# SPv2_2.net
KiCad netlist of a schematic drawn in EAGLE
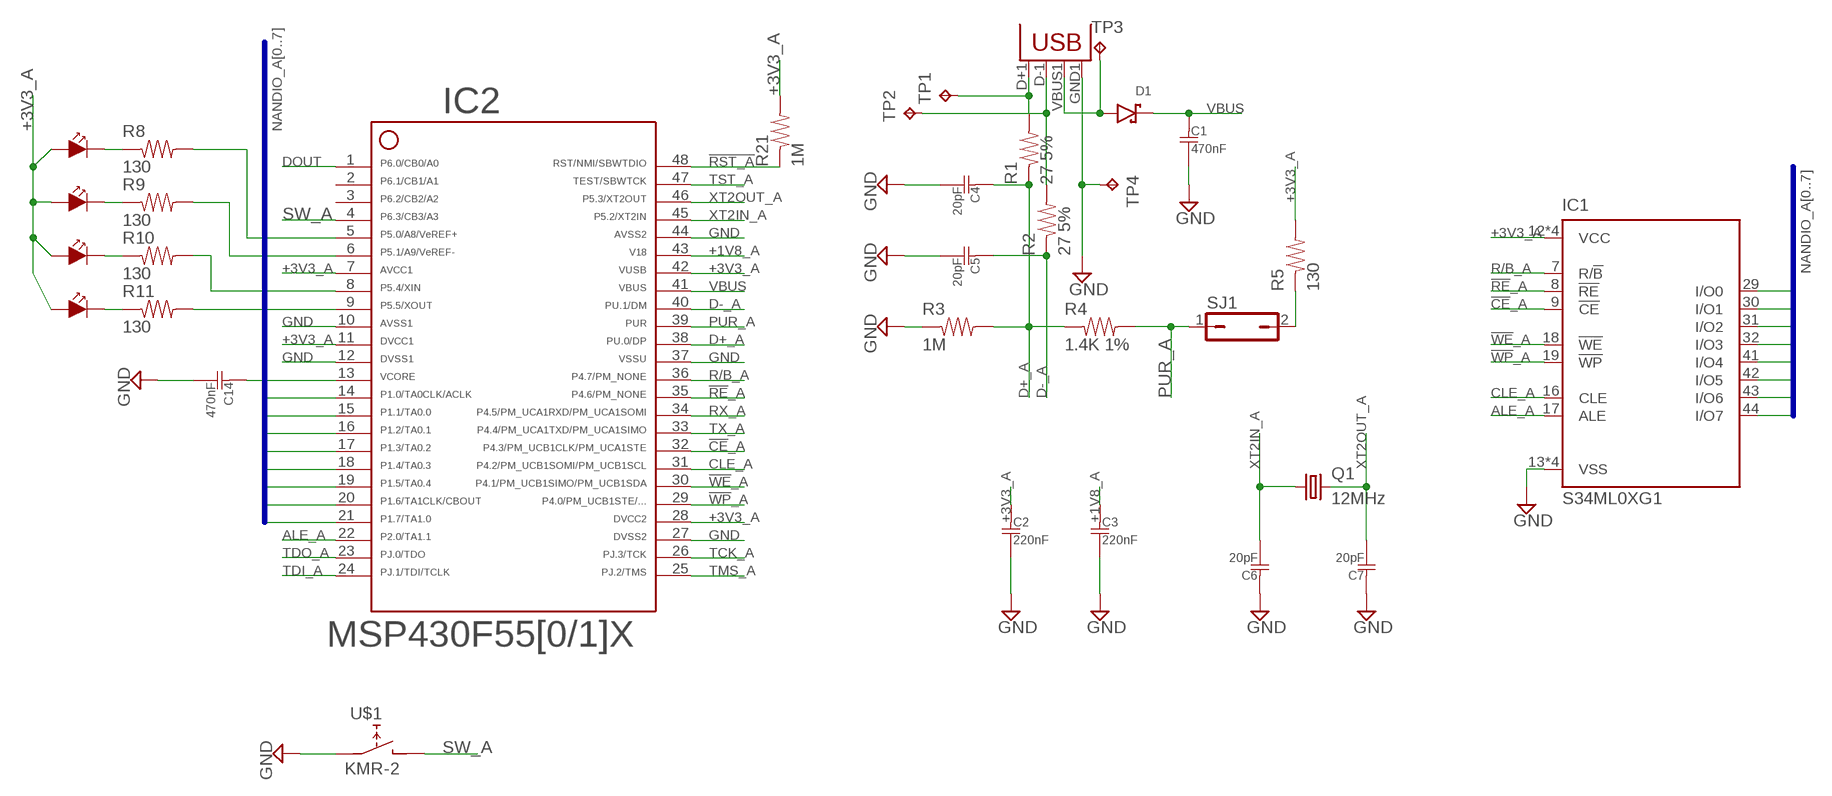
[diagram p0: schematic, sheet 1]
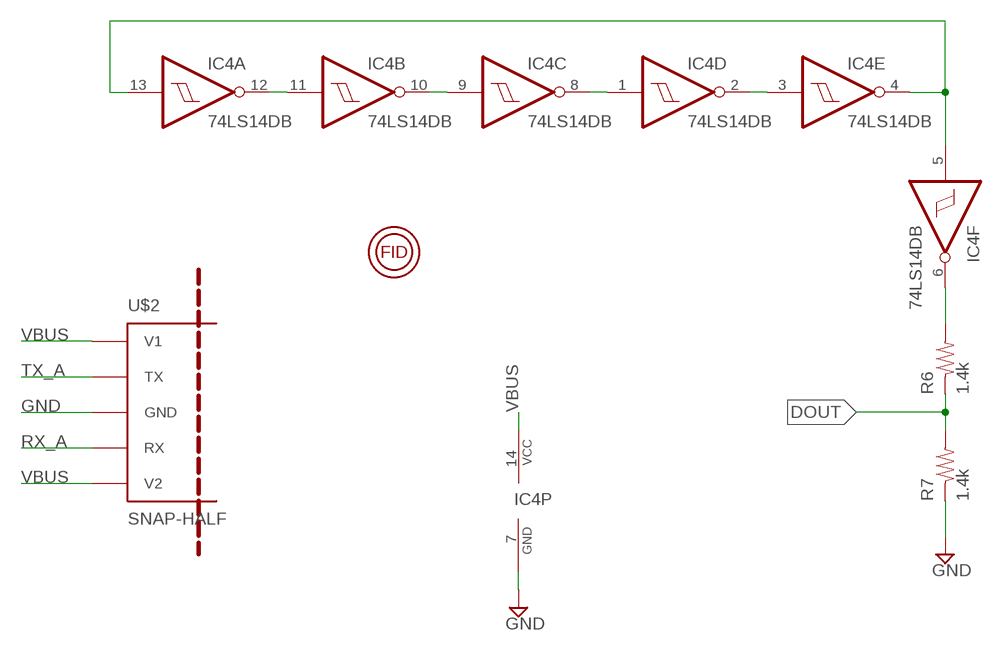
[diagram p1: schematic, sheet 2]

(export (version "E")
  (design (tool "Eeschema 10.0.6"))
  (components
    (comp (ref "IC4")
      (value "74LS14DB")
      (footprint "eagle-import:SSOP14")
      (libsource (lib "eagle-import") (part "7414DBLS"))
    )
    (comp (ref "R6")
      (value "1.4k")
      (footprint "eagle-import:R0805")
      (libsource (lib "eagle-import") (part "R0805"))
    )
    (comp (ref "R7")
      (value "1.4k")
      (footprint "eagle-import:R0805")
      (libsource (lib "eagle-import") (part "R0805"))
    )
    (comp (ref "U$2")
      (value "SNAP-HALF")
      (footprint "eagle-import:SNAP-HALF")
      (libsource (lib "eagle-import") (part "SNAP-HALF"))
    )
    (comp (ref "U$3")
      (value "FIDUCAL")
      (footprint "eagle-import:FIDUCAL")
      (libsource (lib "eagle-import") (part "FIDUCAL"))
    )
    (comp (ref "C1")
      (value "470nF")
      (footprint "eagle-import:R0805")
      (libsource (lib "eagle-import") (part "C0805"))
    )
    (comp (ref "C2")
      (value "220nF")
      (footprint "eagle-import:R0805")
      (libsource (lib "eagle-import") (part "C0805"))
    )
    (comp (ref "C3")
      (value "220nF")
      (footprint "eagle-import:R0805")
      (libsource (lib "eagle-import") (part "C0805"))
    )
    (comp (ref "C4")
      (value "20pF")
      (footprint "eagle-import:R0805")
      (libsource (lib "eagle-import") (part "C0805"))
    )
    (comp (ref "C5")
      (value "20pF")
      (footprint "eagle-import:R0805")
      (libsource (lib "eagle-import") (part "C0805"))
    )
    (comp (ref "C6")
      (value "20pF")
      (footprint "eagle-import:R0805")
      (libsource (lib "eagle-import") (part "C0805"))
    )
    (comp (ref "C7")
      (value "20pF")
      (footprint "eagle-import:R0805")
      (libsource (lib "eagle-import") (part "C0805"))
    )
    (comp (ref "C14")
      (value "470nF")
      (footprint "eagle-import:R0805")
      (libsource (lib "eagle-import") (part "C0805"))
    )
    (comp (ref "D1")
      (value "D-SCHOTTKY")
      (footprint "eagle-import:SOD123")
      (libsource (lib "eagle-import") (part "D-SCHOTTKY"))
    )
    (comp (ref "IC1")
      (value "S34ML0XG1")
      (footprint "eagle-import:TSOP48")
      (libsource (lib "eagle-import") (part "S34ML0XG1"))
    )
    (comp (ref "IC2")
      (value "F5508")
      (footprint "eagle-import:PT48")
      (libsource (lib "eagle-import") (part "F55[0/1]X---PT48"))
    )
    (comp (ref "JP1")
      (value "USBA-SMD-MALE")
      (footprint "eagle-import:USB-A-SMT-MALE")
      (libsource (lib "eagle-import") (part "USBA-SMD-MALE"))
    )
    (comp (ref "Q1")
      (value "12MHz")
      (footprint "eagle-import:CSM-3X")
      (libsource (lib "eagle-import") (part "CRYSTALCSM-3X"))
    )
    (comp (ref "R1")
      (value "27 5%")
      (footprint "eagle-import:R0805")
      (libsource (lib "eagle-import") (part "R0805"))
    )
    (comp (ref "R2")
      (value "27 5%")
      (footprint "eagle-import:R0805")
      (libsource (lib "eagle-import") (part "R0805"))
    )
    (comp (ref "R3")
      (value "1M")
      (footprint "eagle-import:R0805")
      (libsource (lib "eagle-import") (part "R0805"))
    )
    (comp (ref "R4")
      (value "1.4K 1%")
      (footprint "eagle-import:R0805")
      (libsource (lib "eagle-import") (part "R0805"))
    )
    (comp (ref "R5")
      (value "130")
      (footprint "eagle-import:R0805")
      (libsource (lib "eagle-import") (part "R0805"))
    )
    (comp (ref "R8")
      (value "130")
      (footprint "eagle-import:R0805")
      (libsource (lib "eagle-import") (part "R0805"))
    )
    (comp (ref "R9")
      (value "130")
      (footprint "eagle-import:R0805")
      (libsource (lib "eagle-import") (part "R0805"))
    )
    (comp (ref "R10")
      (value "130")
      (footprint "eagle-import:R0805")
      (libsource (lib "eagle-import") (part "R0805"))
    )
    (comp (ref "R11")
      (value "130")
      (footprint "eagle-import:R0805")
      (libsource (lib "eagle-import") (part "R0805"))
    )
    (comp (ref "R21")
      (value "1M")
      (footprint "eagle-import:R0805")
      (libsource (lib "eagle-import") (part "R0805"))
    )
    (comp (ref "SJ1")
      (value "JP1Q")
      (footprint "eagle-import:JP1")
      (libsource (lib "eagle-import") (part "JP1Q"))
    )
    (comp (ref "TP1")
      (value "TPTP13R")
      (footprint "eagle-import:TP13R")
      (libsource (lib "eagle-import") (part "TPTP13R"))
    )
    (comp (ref "TP2")
      (value "TPTP13R")
      (footprint "eagle-import:TP13R")
      (libsource (lib "eagle-import") (part "TPTP13R"))
    )
    (comp (ref "TP3")
      (value "TPTP13R")
      (footprint "eagle-import:TP13R")
      (libsource (lib "eagle-import") (part "TPTP13R"))
    )
    (comp (ref "TP4")
      (value "TPTP13R")
      (footprint "eagle-import:TP13R")
      (libsource (lib "eagle-import") (part "TPTP13R"))
    )
    (comp (ref "U$1")
      (value "KMR-2")
      (footprint "eagle-import:KMR-2-SWITCH")
      (libsource (lib "eagle-import") (part "KMR-2"))
    )
    (comp (ref "U$5")
      (value "LED")
      (footprint "eagle-import:LED0805")
      (libsource (lib "eagle-import") (part "LED"))
    )
    (comp (ref "U$6")
      (value "LED")
      (footprint "eagle-import:LED0805")
      (libsource (lib "eagle-import") (part "LED"))
    )
    (comp (ref "U$7")
      (value "LED")
      (footprint "eagle-import:LED0805")
      (libsource (lib "eagle-import") (part "LED"))
    )
    (comp (ref "U$8")
      (value "LED")
      (footprint "eagle-import:LED0805")
      (libsource (lib "eagle-import") (part "LED"))
    )
  )
  (nets
    (net (code "1") (name "+1V8_A") (class "Default")
      (node (ref "C3") (pin "P$1") (pinfunction "1_P$1") (pintype "passive"))
      (node (ref "IC2") (pin "43") (pinfunction "43_43") (pintype "power_in"))
    )
    (net (code "2") (name "+3V3_A") (class "Default")
      (node (ref "C2") (pin "P$1") (pinfunction "1_P$1") (pintype "passive"))
      (node (ref "IC1") (pin "12") (pinfunction "VCC_12") (pintype "power_in"))
      (node (ref "IC1") (pin "34") (pinfunction "VCC_34") (pintype "power_in"))
      (node (ref "IC1") (pin "37") (pinfunction "VCC_37") (pintype "power_in"))
      (node (ref "IC1") (pin "39") (pinfunction "VCC_39") (pintype "power_in"))
      (node (ref "IC2") (pin "11") (pinfunction "11_11") (pintype "power_in"))
      (node (ref "IC2") (pin "28") (pinfunction "28_28") (pintype "power_in"))
      (node (ref "IC2") (pin "42") (pinfunction "42_42") (pintype "power_in"))
      (node (ref "IC2") (pin "7") (pinfunction "7_7") (pintype "power_in"))
      (node (ref "R21") (pin "P$2") (pinfunction "2_P$2") (pintype "passive"))
      (node (ref "R5") (pin "P$2") (pinfunction "2_P$2") (pintype "passive"))
      (node (ref "U$5") (pin "ANODE") (pinfunction "ANODE_ANODE") (pintype "passive"))
      (node (ref "U$6") (pin "ANODE") (pinfunction "ANODE_ANODE") (pintype "passive"))
      (node (ref "U$7") (pin "ANODE") (pinfunction "ANODE_ANODE") (pintype "passive"))
      (node (ref "U$8") (pin "ANODE") (pinfunction "ANODE_ANODE") (pintype "passive"))
    )
    (net (code "4") (name "ALE_A") (class "Default")
      (node (ref "IC1") (pin "17") (pinfunction "ALE_17") (pintype "input"))
      (node (ref "IC2") (pin "22") (pinfunction "22_22") (pintype "bidirectional"))
    )
    (net (code "5") (name "CLE_A") (class "Default")
      (node (ref "IC1") (pin "16") (pinfunction "CLE_16") (pintype "input"))
      (node (ref "IC2") (pin "31") (pinfunction "31_31") (pintype "bidirectional"))
    )
    (net (code "6") (name "D+_A") (class "Default")
      (node (ref "C4") (pin "P$1") (pinfunction "1_P$1") (pintype "passive"))
      (node (ref "IC2") (pin "38") (pinfunction "38_38") (pintype "bidirectional"))
      (node (ref "R1") (pin "P$1") (pinfunction "1_P$1") (pintype "passive"))
      (node (ref "R3") (pin "P$2") (pinfunction "2_P$2") (pintype "passive"))
      (node (ref "R4") (pin "P$1") (pinfunction "1_P$1") (pintype "passive"))
    )
    (net (code "7") (name "D-_A") (class "Default")
      (node (ref "C5") (pin "P$1") (pinfunction "1_P$1") (pintype "passive"))
      (node (ref "IC2") (pin "40") (pinfunction "40_40") (pintype "bidirectional"))
      (node (ref "R2") (pin "P$1") (pinfunction "1_P$1") (pintype "passive"))
    )
    (net (code "8") (name "DOUT") (class "Default")
      (node (ref "IC2") (pin "1") (pinfunction "1_1") (pintype "bidirectional"))
      (node (ref "R6") (pin "P$1") (pinfunction "1_P$1") (pintype "passive"))
      (node (ref "R7") (pin "P$2") (pinfunction "2_P$2") (pintype "passive"))
    )
    (net (code "9") (name "GND") (class "Default")
      (node (ref "C1") (pin "P$2") (pinfunction "2_P$2") (pintype "passive"))
      (node (ref "C14") (pin "P$2") (pinfunction "2_P$2") (pintype "passive"))
      (node (ref "C2") (pin "P$2") (pinfunction "2_P$2") (pintype "passive"))
      (node (ref "C3") (pin "P$2") (pinfunction "2_P$2") (pintype "passive"))
      (node (ref "C4") (pin "P$2") (pinfunction "2_P$2") (pintype "passive"))
      (node (ref "C5") (pin "P$2") (pinfunction "2_P$2") (pintype "passive"))
      (node (ref "C6") (pin "P$1") (pinfunction "1_P$1") (pintype "passive"))
      (node (ref "C7") (pin "P$1") (pinfunction "1_P$1") (pintype "passive"))
      (node (ref "IC1") (pin "13") (pinfunction "VSS_13") (pintype "power_in"))
      (node (ref "IC1") (pin "25") (pinfunction "VSS_25") (pintype "power_in"))
      (node (ref "IC1") (pin "36") (pinfunction "VSS_36") (pintype "power_in"))
      (node (ref "IC1") (pin "48") (pinfunction "VSS_48") (pintype "power_in"))
      (node (ref "IC2") (pin "10") (pinfunction "10_10") (pintype "power_in"))
      (node (ref "IC2") (pin "12") (pinfunction "12_12") (pintype "power_in"))
      (node (ref "IC2") (pin "27") (pinfunction "27_27") (pintype "power_in"))
      (node (ref "IC2") (pin "37") (pinfunction "37_37") (pintype "power_in"))
      (node (ref "IC2") (pin "44") (pinfunction "44_44") (pintype "power_in"))
      (node (ref "IC4") (pin "7") (pinfunction "GND_7") (pintype "power_in"))
      (node (ref "JP1") (pin "GND1") (pinfunction "GND_GND1") (pintype "bidirectional"))
      (node (ref "R3") (pin "P$1") (pinfunction "1_P$1") (pintype "passive"))
      (node (ref "R7") (pin "P$1") (pinfunction "1_P$1") (pintype "passive"))
      (node (ref "TP4") (pin "TP") (pinfunction "TP_TP") (pintype "input"))
      (node (ref "U$1") (pin "PA1") (pinfunction "A1_PA1") (pintype "passive"))
      (node (ref "U$1") (pin "PA2") (pinfunction "A1_PA2") (pintype "passive"))
      (node (ref "U$2") (pin "P$3") (pinfunction "GND_P$3") (pintype "bidirectional"))
    )
    (net (code "10") (name "NANDIO_A0") (class "Default")
      (node (ref "IC1") (pin "29") (pinfunction "I/O0_29") (pintype "bidirectional"))
      (node (ref "IC2") (pin "14") (pinfunction "14_14") (pintype "bidirectional"))
    )
    (net (code "11") (name "NANDIO_A1") (class "Default")
      (node (ref "IC1") (pin "30") (pinfunction "I/O1_30") (pintype "bidirectional"))
      (node (ref "IC2") (pin "15") (pinfunction "15_15") (pintype "bidirectional"))
    )
    (net (code "12") (name "NANDIO_A2") (class "Default")
      (node (ref "IC1") (pin "31") (pinfunction "I/O2_31") (pintype "bidirectional"))
      (node (ref "IC2") (pin "16") (pinfunction "16_16") (pintype "bidirectional"))
    )
    (net (code "13") (name "NANDIO_A3") (class "Default")
      (node (ref "IC1") (pin "32") (pinfunction "I/O3_32") (pintype "bidirectional"))
      (node (ref "IC2") (pin "17") (pinfunction "17_17") (pintype "bidirectional"))
    )
    (net (code "14") (name "NANDIO_A4") (class "Default")
      (node (ref "IC1") (pin "41") (pinfunction "I/O4_41") (pintype "bidirectional"))
      (node (ref "IC2") (pin "18") (pinfunction "18_18") (pintype "bidirectional"))
    )
    (net (code "15") (name "NANDIO_A5") (class "Default")
      (node (ref "IC1") (pin "42") (pinfunction "I/O5_42") (pintype "bidirectional"))
      (node (ref "IC2") (pin "19") (pinfunction "19_19") (pintype "bidirectional"))
    )
    (net (code "16") (name "NANDIO_A6") (class "Default")
      (node (ref "IC1") (pin "43") (pinfunction "I/O6_43") (pintype "bidirectional"))
      (node (ref "IC2") (pin "20") (pinfunction "20_20") (pintype "bidirectional"))
    )
    (net (code "17") (name "NANDIO_A7") (class "Default")
      (node (ref "IC1") (pin "44") (pinfunction "I/O7_44") (pintype "bidirectional"))
      (node (ref "IC2") (pin "21") (pinfunction "21_21") (pintype "bidirectional"))
    )
    (net (code "18") (name "Net-(C14-1)") (class "Default")
      (node (ref "C14") (pin "P$1") (pinfunction "1_P$1") (pintype "passive"))
      (node (ref "IC2") (pin "13") (pinfunction "13_13") (pintype "power_in"))
    )
    (net (code "19") (name "Net-(IC4A-I)") (class "Default")
      (node (ref "IC4") (pin "13") (pinfunction "I_13") (pintype "input"))
      (node (ref "IC4") (pin "4") (pinfunction "O_4") (pintype "output"))
      (node (ref "IC4") (pin "5") (pinfunction "I_5") (pintype "input"))
    )
    (net (code "20") (name "Net-(IC4A-O)") (class "Default")
      (node (ref "IC4") (pin "11") (pinfunction "I_11") (pintype "input"))
      (node (ref "IC4") (pin "12") (pinfunction "O_12") (pintype "output"))
    )
    (net (code "21") (name "Net-(IC4B-O)") (class "Default")
      (node (ref "IC4") (pin "10") (pinfunction "O_10") (pintype "output"))
      (node (ref "IC4") (pin "9") (pinfunction "I_9") (pintype "input"))
    )
    (net (code "22") (name "Net-(IC4C-O)") (class "Default")
      (node (ref "IC4") (pin "1") (pinfunction "I_1") (pintype "input"))
      (node (ref "IC4") (pin "8") (pinfunction "O_8") (pintype "output"))
    )
    (net (code "23") (name "Net-(IC4D-O)") (class "Default")
      (node (ref "IC4") (pin "2") (pinfunction "O_2") (pintype "output"))
      (node (ref "IC4") (pin "3") (pinfunction "I_3") (pintype "input"))
    )
    (net (code "24") (name "Net-(IC4F-O)") (class "Default")
      (node (ref "IC4") (pin "6") (pinfunction "O_6") (pintype "output"))
      (node (ref "R6") (pin "P$2") (pinfunction "2_P$2") (pintype "passive"))
    )
    (net (code "25") (name "Net-(JP1-D+)") (class "Default")
      (node (ref "JP1") (pin "D+1") (pinfunction "D+_D+1") (pintype "bidirectional"))
      (node (ref "R1") (pin "P$2") (pinfunction "2_P$2") (pintype "passive"))
      (node (ref "TP1") (pin "TP") (pinfunction "TP_TP") (pintype "input"))
    )
    (net (code "26") (name "Net-(JP1-D-)") (class "Default")
      (node (ref "JP1") (pin "D-1") (pinfunction "D-_D-1") (pintype "bidirectional"))
      (node (ref "R2") (pin "P$2") (pinfunction "2_P$2") (pintype "passive"))
      (node (ref "TP2") (pin "TP") (pinfunction "TP_TP") (pintype "input"))
    )
    (net (code "27") (name "Net-(JP1-VBUS)") (class "Default")
      (node (ref "D1") (pin "ANODE") (pinfunction "ANODE_ANODE") (pintype "passive"))
      (node (ref "JP1") (pin "VBUS1") (pinfunction "VBUS_VBUS1") (pintype "bidirectional"))
      (node (ref "TP3") (pin "TP") (pinfunction "TP_TP") (pintype "input"))
    )
    (net (code "28") (name "Net-(R5-1)") (class "Default")
      (node (ref "R5") (pin "P$1") (pinfunction "1_P$1") (pintype "passive"))
      (node (ref "SJ1") (pin "2") (pinfunction "2_2") (pintype "passive"))
    )
    (net (code "29") (name "Net-(R8-1)") (class "Default")
      (node (ref "R8") (pin "P$1") (pinfunction "1_P$1") (pintype "passive"))
      (node (ref "U$5") (pin "CATHODE") (pinfunction "CATHODE_CATHODE") (pintype "passive"))
    )
    (net (code "30") (name "Net-(R8-2)") (class "Default")
      (node (ref "IC2") (pin "5") (pinfunction "5_5") (pintype "bidirectional"))
      (node (ref "R8") (pin "P$2") (pinfunction "2_P$2") (pintype "passive"))
    )
    (net (code "31") (name "Net-(R9-1)") (class "Default")
      (node (ref "R9") (pin "P$1") (pinfunction "1_P$1") (pintype "passive"))
      (node (ref "U$6") (pin "CATHODE") (pinfunction "CATHODE_CATHODE") (pintype "passive"))
    )
    (net (code "32") (name "Net-(R9-2)") (class "Default")
      (node (ref "IC2") (pin "6") (pinfunction "6_6") (pintype "bidirectional"))
      (node (ref "R9") (pin "P$2") (pinfunction "2_P$2") (pintype "passive"))
    )
    (net (code "33") (name "Net-(R10-1)") (class "Default")
      (node (ref "R10") (pin "P$1") (pinfunction "1_P$1") (pintype "passive"))
      (node (ref "U$7") (pin "CATHODE") (pinfunction "CATHODE_CATHODE") (pintype "passive"))
    )
    (net (code "34") (name "Net-(R10-2)") (class "Default")
      (node (ref "IC2") (pin "8") (pinfunction "8_8") (pintype "bidirectional"))
      (node (ref "R10") (pin "P$2") (pinfunction "2_P$2") (pintype "passive"))
    )
    (net (code "35") (name "Net-(R11-1)") (class "Default")
      (node (ref "R11") (pin "P$1") (pinfunction "1_P$1") (pintype "passive"))
      (node (ref "U$8") (pin "CATHODE") (pinfunction "CATHODE_CATHODE") (pintype "passive"))
    )
    (net (code "36") (name "Net-(R11-2)") (class "Default")
      (node (ref "IC2") (pin "9") (pinfunction "9_9") (pintype "bidirectional"))
      (node (ref "R11") (pin "P$2") (pinfunction "2_P$2") (pintype "passive"))
    )
    (net (code "37") (name "PUR_A") (class "Default")
      (node (ref "IC2") (pin "39") (pinfunction "39_39") (pintype "bidirectional"))
      (node (ref "R4") (pin "P$2") (pinfunction "2_P$2") (pintype "passive"))
      (node (ref "SJ1") (pin "1") (pinfunction "1_1") (pintype "passive"))
    )
    (net (code "38") (name "RX_A") (class "Default")
      (node (ref "IC2") (pin "34") (pinfunction "34_34") (pintype "bidirectional"))
      (node (ref "U$2") (pin "P$4") (pinfunction "RX_P$4") (pintype "bidirectional"))
    )
    (net (code "39") (name "R{slash}B_A") (class "Default")
      (node (ref "IC1") (pin "7") (pinfunction "R/~{B}_7") (pintype "input"))
      (node (ref "IC2") (pin "36") (pinfunction "36_36") (pintype "bidirectional"))
    )
    (net (code "40") (name "SW_A") (class "Default")
      (node (ref "IC2") (pin "4") (pinfunction "4_4") (pintype "bidirectional"))
      (node (ref "U$1") (pin "PB1") (pinfunction "B_PB1") (pintype "passive"))
      (node (ref "U$1") (pin "PB2") (pinfunction "B_PB2") (pintype "passive"))
    )
    (net (code "41") (name "TCK_A") (class "Default")
      (node (ref "IC2") (pin "26") (pinfunction "26_26") (pintype "bidirectional"))
    )
    (net (code "42") (name "TDI_A") (class "Default")
      (node (ref "IC2") (pin "24") (pinfunction "24_24") (pintype "bidirectional"))
    )
    (net (code "43") (name "TDO_A") (class "Default")
      (node (ref "IC2") (pin "23") (pinfunction "23_23") (pintype "bidirectional"))
    )
    (net (code "44") (name "TMS_A") (class "Default")
      (node (ref "IC2") (pin "25") (pinfunction "25_25") (pintype "bidirectional"))
    )
    (net (code "45") (name "TST_A") (class "Default")
      (node (ref "IC2") (pin "47") (pinfunction "47_47") (pintype "input"))
    )
    (net (code "46") (name "TX_A") (class "Default")
      (node (ref "IC2") (pin "33") (pinfunction "33_33") (pintype "bidirectional"))
      (node (ref "U$2") (pin "P$2") (pinfunction "TX_P$2") (pintype "bidirectional"))
    )
    (net (code "47") (name "VBUS") (class "Default")
      (node (ref "C1") (pin "P$1") (pinfunction "1_P$1") (pintype "passive"))
      (node (ref "D1") (pin "CATHODE") (pinfunction "CATHODE_CATHODE") (pintype "passive"))
      (node (ref "IC2") (pin "41") (pinfunction "41_41") (pintype "power_in"))
      (node (ref "IC4") (pin "14") (pinfunction "VCC_14") (pintype "power_in"))
      (node (ref "U$2") (pin "P$1") (pinfunction "V1_P$1") (pintype "bidirectional"))
      (node (ref "U$2") (pin "P$5") (pinfunction "V2_P$5") (pintype "bidirectional"))
    )
    (net (code "48") (name "XT2IN_A") (class "Default")
      (node (ref "C6") (pin "P$2") (pinfunction "2_P$2") (pintype "passive"))
      (node (ref "IC2") (pin "45") (pinfunction "45_45") (pintype "bidirectional"))
      (node (ref "Q1") (pin "P$1") (pinfunction "1_P$1") (pintype "passive"))
    )
    (net (code "49") (name "XT2OUT_A") (class "Default")
      (node (ref "C7") (pin "P$2") (pinfunction "2_P$2") (pintype "passive"))
      (node (ref "IC2") (pin "46") (pinfunction "46_46") (pintype "power_in"))
      (node (ref "Q1") (pin "P$2") (pinfunction "2_P$2") (pintype "passive"))
    )
    (net (code "50") (name "unconnected-(IC2-Pad2)") (class "Default")
      (node (ref "IC2") (pin "2") (pinfunction "2_2") (pintype "bidirectional"))
    )
    (net (code "51") (name "unconnected-(IC2-Pad3)") (class "Default")
      (node (ref "IC2") (pin "3") (pinfunction "3_3") (pintype "bidirectional"))
    )
    (net (code "52") (name "~{CE}_A") (class "Default")
      (node (ref "IC1") (pin "9") (pinfunction "~{CE}_9") (pintype "input"))
      (node (ref "IC2") (pin "32") (pinfunction "32_32") (pintype "bidirectional"))
    )
    (net (code "53") (name "~{RE}_A") (class "Default")
      (node (ref "IC1") (pin "8") (pinfunction "~{RE}_8") (pintype "input"))
      (node (ref "IC2") (pin "35") (pinfunction "35_35") (pintype "bidirectional"))
    )
    (net (code "54") (name "~{RST_A}") (class "Default")
      (node (ref "IC2") (pin "48") (pinfunction "48_48") (pintype "bidirectional"))
      (node (ref "R21") (pin "P$1") (pinfunction "1_P$1") (pintype "passive"))
    )
    (net (code "55") (name "~{WE}_A") (class "Default")
      (node (ref "IC1") (pin "18") (pinfunction "~{WE}_18") (pintype "input"))
      (node (ref "IC2") (pin "30") (pinfunction "30_30") (pintype "bidirectional"))
    )
    (net (code "56") (name "~{WP}_A") (class "Default")
      (node (ref "IC1") (pin "19") (pinfunction "~{WP}_19") (pintype "input"))
      (node (ref "IC2") (pin "29") (pinfunction "29_29") (pintype "bidirectional"))
    )
  )
)
